# demo2.net
KiCad netlist of a schematic drawn in EAGLE
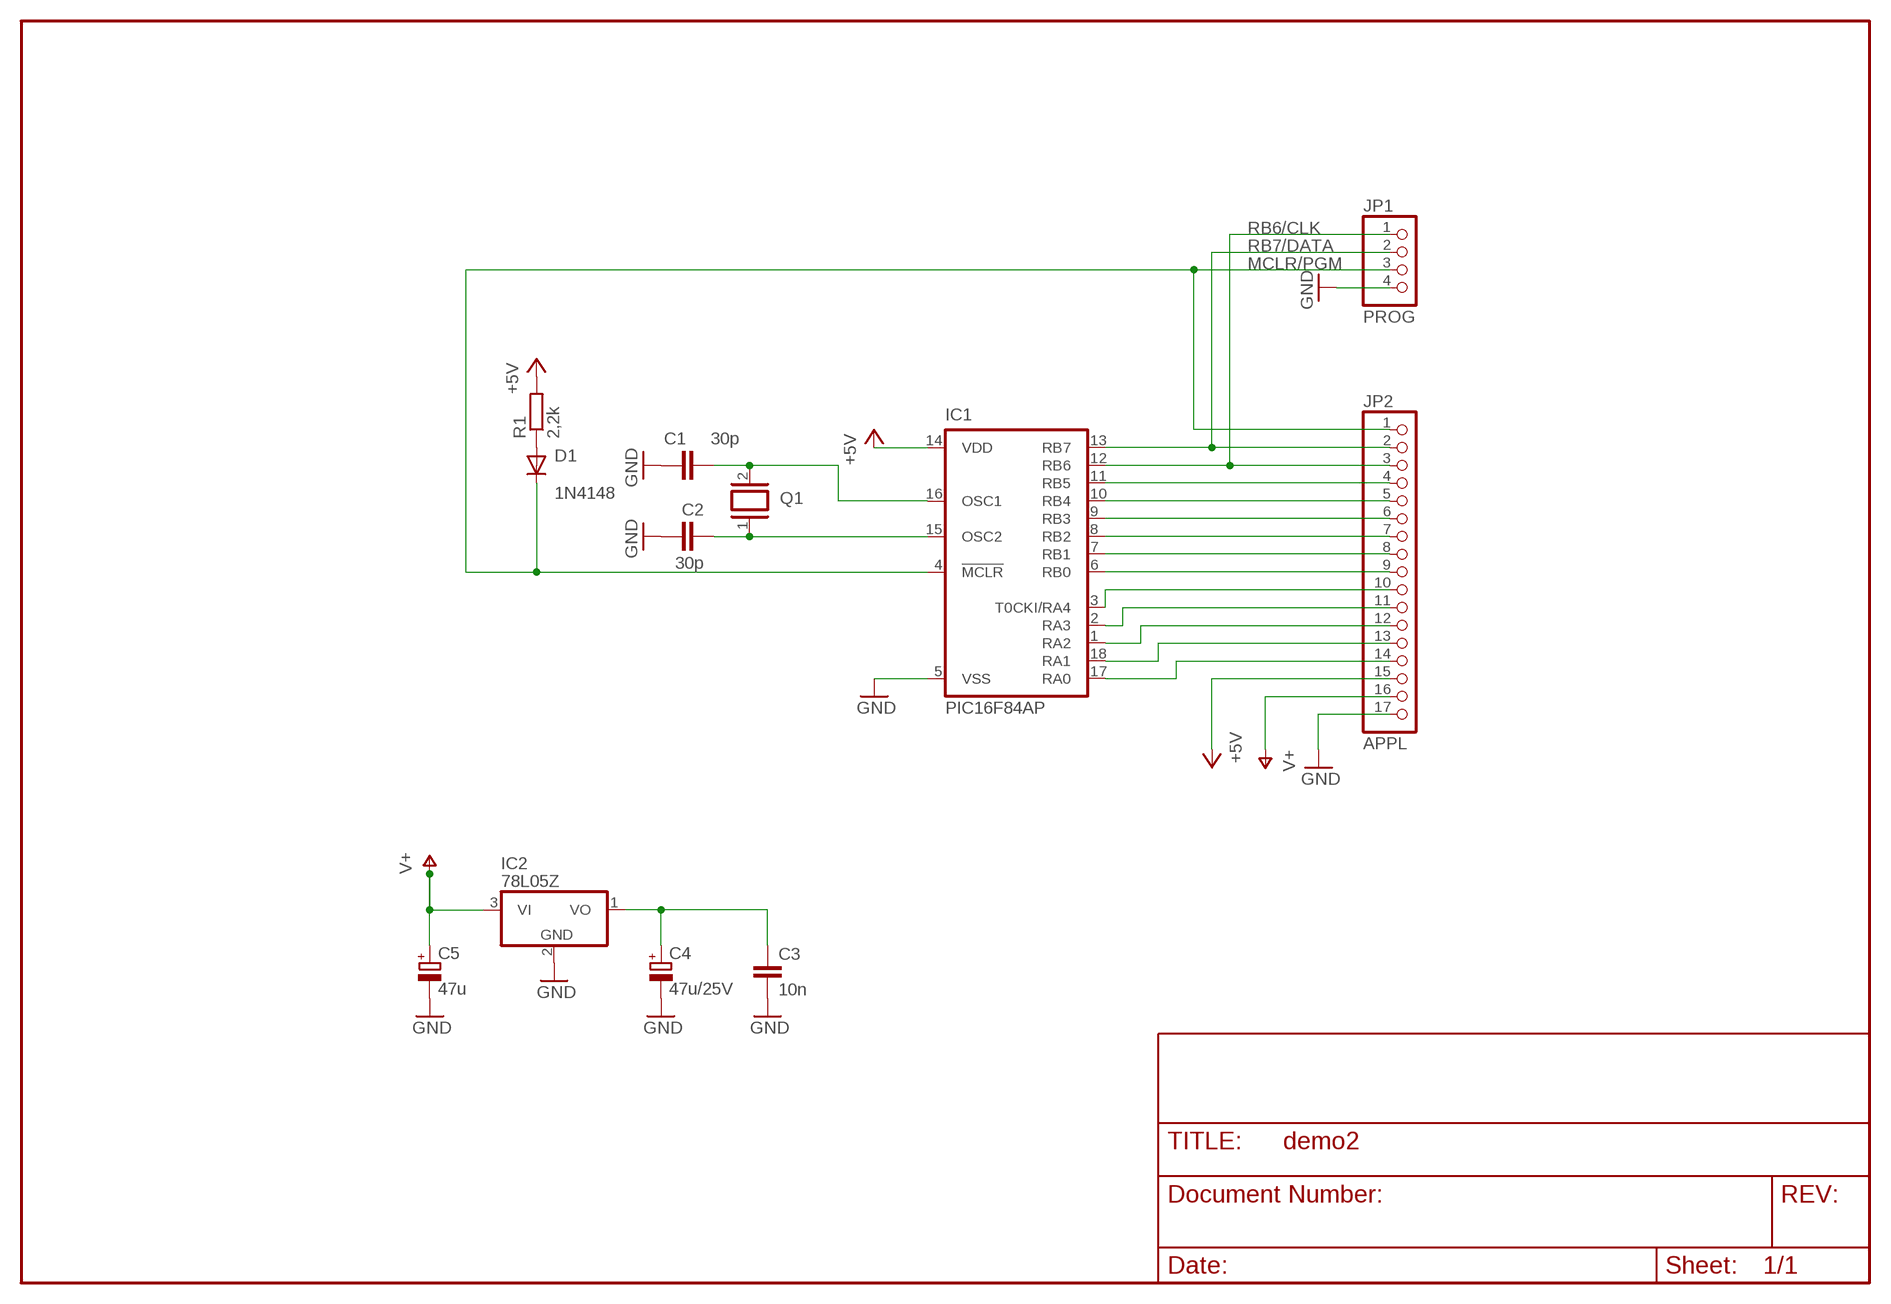
[diagram p0: schematic, sheet 1]

(export (version "E")
  (design (tool "Eeschema 10.0.6"))
  (components
    (comp (ref "C1")
      (value "30p")
      (footprint "eagle-import:C1206")
      (libsource (lib "eagle-import") (part "C-EUC1206"))
    )
    (comp (ref "C2")
      (value "30p")
      (footprint "eagle-import:C1206")
      (libsource (lib "eagle-import") (part "C-EUC1206"))
    )
    (comp (ref "C3")
      (value "10n")
      (footprint "eagle-import:C025-025X050")
      (libsource (lib "eagle-import") (part "C-EU025-025X050"))
    )
    (comp (ref "C4")
      (value "47u/25V")
      (footprint "eagle-import:TAP5-45")
      (libsource (lib "eagle-import") (part "CPOL-EUTAP5-45"))
    )
    (comp (ref "C5")
      (value "47u")
      (footprint "eagle-import:TAP5-45")
      (libsource (lib "eagle-import") (part "CPOL-EUTAP5-45"))
    )
    (comp (ref "D1")
      (value "1N4148")
      (footprint "eagle-import:DO35-10")
      (libsource (lib "eagle-import") (part "1N4148"))
    )
    (comp (ref "IC1")
      (value "PIC16F84AP")
      (footprint "eagle-import:DIL18")
      (libsource (lib "eagle-import") (part "PIC16F8P4A"))
    )
    (comp (ref "IC2")
      (value "78L05Z")
      (footprint "eagle-import:TO92")
      (libsource (lib "eagle-import") (part "78ZL05"))
    )
    (comp (ref "JP1")
      (value "PROG")
      (footprint "eagle-import:1X04")
      (libsource (lib "eagle-import") (part "PINHD-1X4"))
    )
    (comp (ref "JP2")
      (value "APPL")
      (footprint "eagle-import:1X17")
      (libsource (lib "eagle-import") (part "PINHD-1X17"))
    )
    (comp (ref "Q1")
      (value "XTAL/S")
      (footprint "eagle-import:QS")
      (libsource (lib "eagle-import") (part "XTAL/S"))
    )
    (comp (ref "R1")
      (value "2,2k")
      (footprint "eagle-import:R1206")
      (libsource (lib "eagle-import") (part "R-EU_R1206"))
    )
  )
  (nets
    (net (code "1") (name "+5V") (class "Default")
      (node (ref "IC1") (pin "14") (pinfunction "VDD_14") (pintype "power_in"))
      (node (ref "JP2") (pin "15") (pinfunction "15_15") (pintype "passive"))
      (node (ref "R1") (pin "1") (pinfunction "2_1") (pintype "passive"))
    )
    (net (code "2") (name "/MCLR{slash}PGM") (class "Default")
      (node (ref "D1") (pin "C") (pinfunction "C_C") (pintype "passive"))
      (node (ref "IC1") (pin "4") (pinfunction "~{MCLR}_4") (pintype "input"))
      (node (ref "JP1") (pin "3") (pinfunction "3_3") (pintype "passive"))
      (node (ref "JP2") (pin "1") (pinfunction "1_1") (pintype "passive"))
    )
    (net (code "3") (name "/RB6{slash}CLK") (class "Default")
      (node (ref "IC1") (pin "12") (pinfunction "RB6_12") (pintype "bidirectional"))
      (node (ref "JP1") (pin "1") (pinfunction "1_1") (pintype "passive"))
      (node (ref "JP2") (pin "3") (pinfunction "3_3") (pintype "passive"))
    )
    (net (code "4") (name "/RB7{slash}DATA") (class "Default")
      (node (ref "IC1") (pin "13") (pinfunction "RB7_13") (pintype "bidirectional"))
      (node (ref "JP1") (pin "2") (pinfunction "2_2") (pintype "passive"))
      (node (ref "JP2") (pin "2") (pinfunction "2_2") (pintype "passive"))
    )
    (net (code "5") (name "GND") (class "Default")
      (node (ref "C1") (pin "1") (pinfunction "1_1") (pintype "passive"))
      (node (ref "C2") (pin "1") (pinfunction "1_1") (pintype "passive"))
      (node (ref "C3") (pin "2") (pinfunction "2_2") (pintype "passive"))
      (node (ref "C4") (pin "-") (pinfunction "-_-") (pintype "passive"))
      (node (ref "C5") (pin "-") (pinfunction "-_-") (pintype "passive"))
      (node (ref "IC1") (pin "5") (pinfunction "VSS_5") (pintype "power_in"))
      (node (ref "IC2") (pin "2") (pinfunction "GND_2") (pintype "passive"))
      (node (ref "JP1") (pin "4") (pinfunction "4_4") (pintype "passive"))
      (node (ref "JP2") (pin "17") (pinfunction "17_17") (pintype "passive"))
    )
    (net (code "6") (name "Net-(IC1-OSC1)") (class "Default")
      (node (ref "C1") (pin "2") (pinfunction "2_2") (pintype "passive"))
      (node (ref "IC1") (pin "16") (pinfunction "OSC1_16") (pintype "input"))
      (node (ref "Q1") (pin "2") (pinfunction "2_2") (pintype "passive"))
    )
    (net (code "7") (name "Net-(IC1-OSC2)") (class "Default")
      (node (ref "C2") (pin "2") (pinfunction "2_2") (pintype "passive"))
      (node (ref "IC1") (pin "15") (pinfunction "OSC2_15") (pintype "output"))
      (node (ref "Q1") (pin "1") (pinfunction "1_1") (pintype "passive"))
    )
    (net (code "8") (name "Net-(IC1-RA0)") (class "Default")
      (node (ref "IC1") (pin "17") (pinfunction "RA0_17") (pintype "bidirectional"))
      (node (ref "JP2") (pin "14") (pinfunction "14_14") (pintype "passive"))
    )
    (net (code "9") (name "Net-(IC1-RA1)") (class "Default")
      (node (ref "IC1") (pin "18") (pinfunction "RA1_18") (pintype "bidirectional"))
      (node (ref "JP2") (pin "13") (pinfunction "13_13") (pintype "passive"))
    )
    (net (code "10") (name "Net-(IC1-RA2)") (class "Default")
      (node (ref "IC1") (pin "1") (pinfunction "RA2_1") (pintype "bidirectional"))
      (node (ref "JP2") (pin "12") (pinfunction "12_12") (pintype "passive"))
    )
    (net (code "11") (name "Net-(IC1-RA3)") (class "Default")
      (node (ref "IC1") (pin "2") (pinfunction "RA3_2") (pintype "bidirectional"))
      (node (ref "JP2") (pin "11") (pinfunction "11_11") (pintype "passive"))
    )
    (net (code "12") (name "Net-(IC1-RB0)") (class "Default")
      (node (ref "IC1") (pin "6") (pinfunction "RB0_6") (pintype "bidirectional"))
      (node (ref "JP2") (pin "9") (pinfunction "9_9") (pintype "passive"))
    )
    (net (code "13") (name "Net-(IC1-RB1)") (class "Default")
      (node (ref "IC1") (pin "7") (pinfunction "RB1_7") (pintype "bidirectional"))
      (node (ref "JP2") (pin "8") (pinfunction "8_8") (pintype "passive"))
    )
    (net (code "14") (name "Net-(IC1-RB2)") (class "Default")
      (node (ref "IC1") (pin "8") (pinfunction "RB2_8") (pintype "bidirectional"))
      (node (ref "JP2") (pin "7") (pinfunction "7_7") (pintype "passive"))
    )
    (net (code "15") (name "Net-(IC1-RB3)") (class "Default")
      (node (ref "IC1") (pin "9") (pinfunction "RB3_9") (pintype "bidirectional"))
      (node (ref "JP2") (pin "6") (pinfunction "6_6") (pintype "passive"))
    )
    (net (code "16") (name "Net-(IC1-RB4)") (class "Default")
      (node (ref "IC1") (pin "10") (pinfunction "RB4_10") (pintype "bidirectional"))
      (node (ref "JP2") (pin "5") (pinfunction "5_5") (pintype "passive"))
    )
    (net (code "17") (name "Net-(IC1-RB5)") (class "Default")
      (node (ref "IC1") (pin "11") (pinfunction "RB5_11") (pintype "bidirectional"))
      (node (ref "JP2") (pin "4") (pinfunction "4_4") (pintype "passive"))
    )
    (net (code "18") (name "Net-(IC1-T0CKI{slash}RA4)") (class "Default")
      (node (ref "IC1") (pin "3") (pinfunction "T0CKI/RA4_3") (pintype "bidirectional"))
      (node (ref "JP2") (pin "10") (pinfunction "10_10") (pintype "passive"))
    )
    (net (code "19") (name "Net-(IC2-VO)") (class "Default")
      (node (ref "C3") (pin "1") (pinfunction "1_1") (pintype "passive"))
      (node (ref "C4") (pin "+") (pinfunction "+_+") (pintype "passive"))
      (node (ref "IC2") (pin "1") (pinfunction "VO_1") (pintype "passive"))
    )
    (net (code "20") (name "Net-(R1-1)") (class "Default")
      (node (ref "D1") (pin "A") (pinfunction "A_A") (pintype "passive"))
      (node (ref "R1") (pin "2") (pinfunction "1_2") (pintype "passive"))
    )
    (net (code "21") (name "V+") (class "Default")
      (node (ref "C5") (pin "+") (pinfunction "+_+") (pintype "passive"))
      (node (ref "IC2") (pin "3") (pinfunction "VI_3") (pintype "input"))
      (node (ref "JP2") (pin "16") (pinfunction "16_16") (pintype "passive"))
    )
  )
)
